# GCM_SCH.net
KiCad netlist of a schematic drawn in Altium Designer
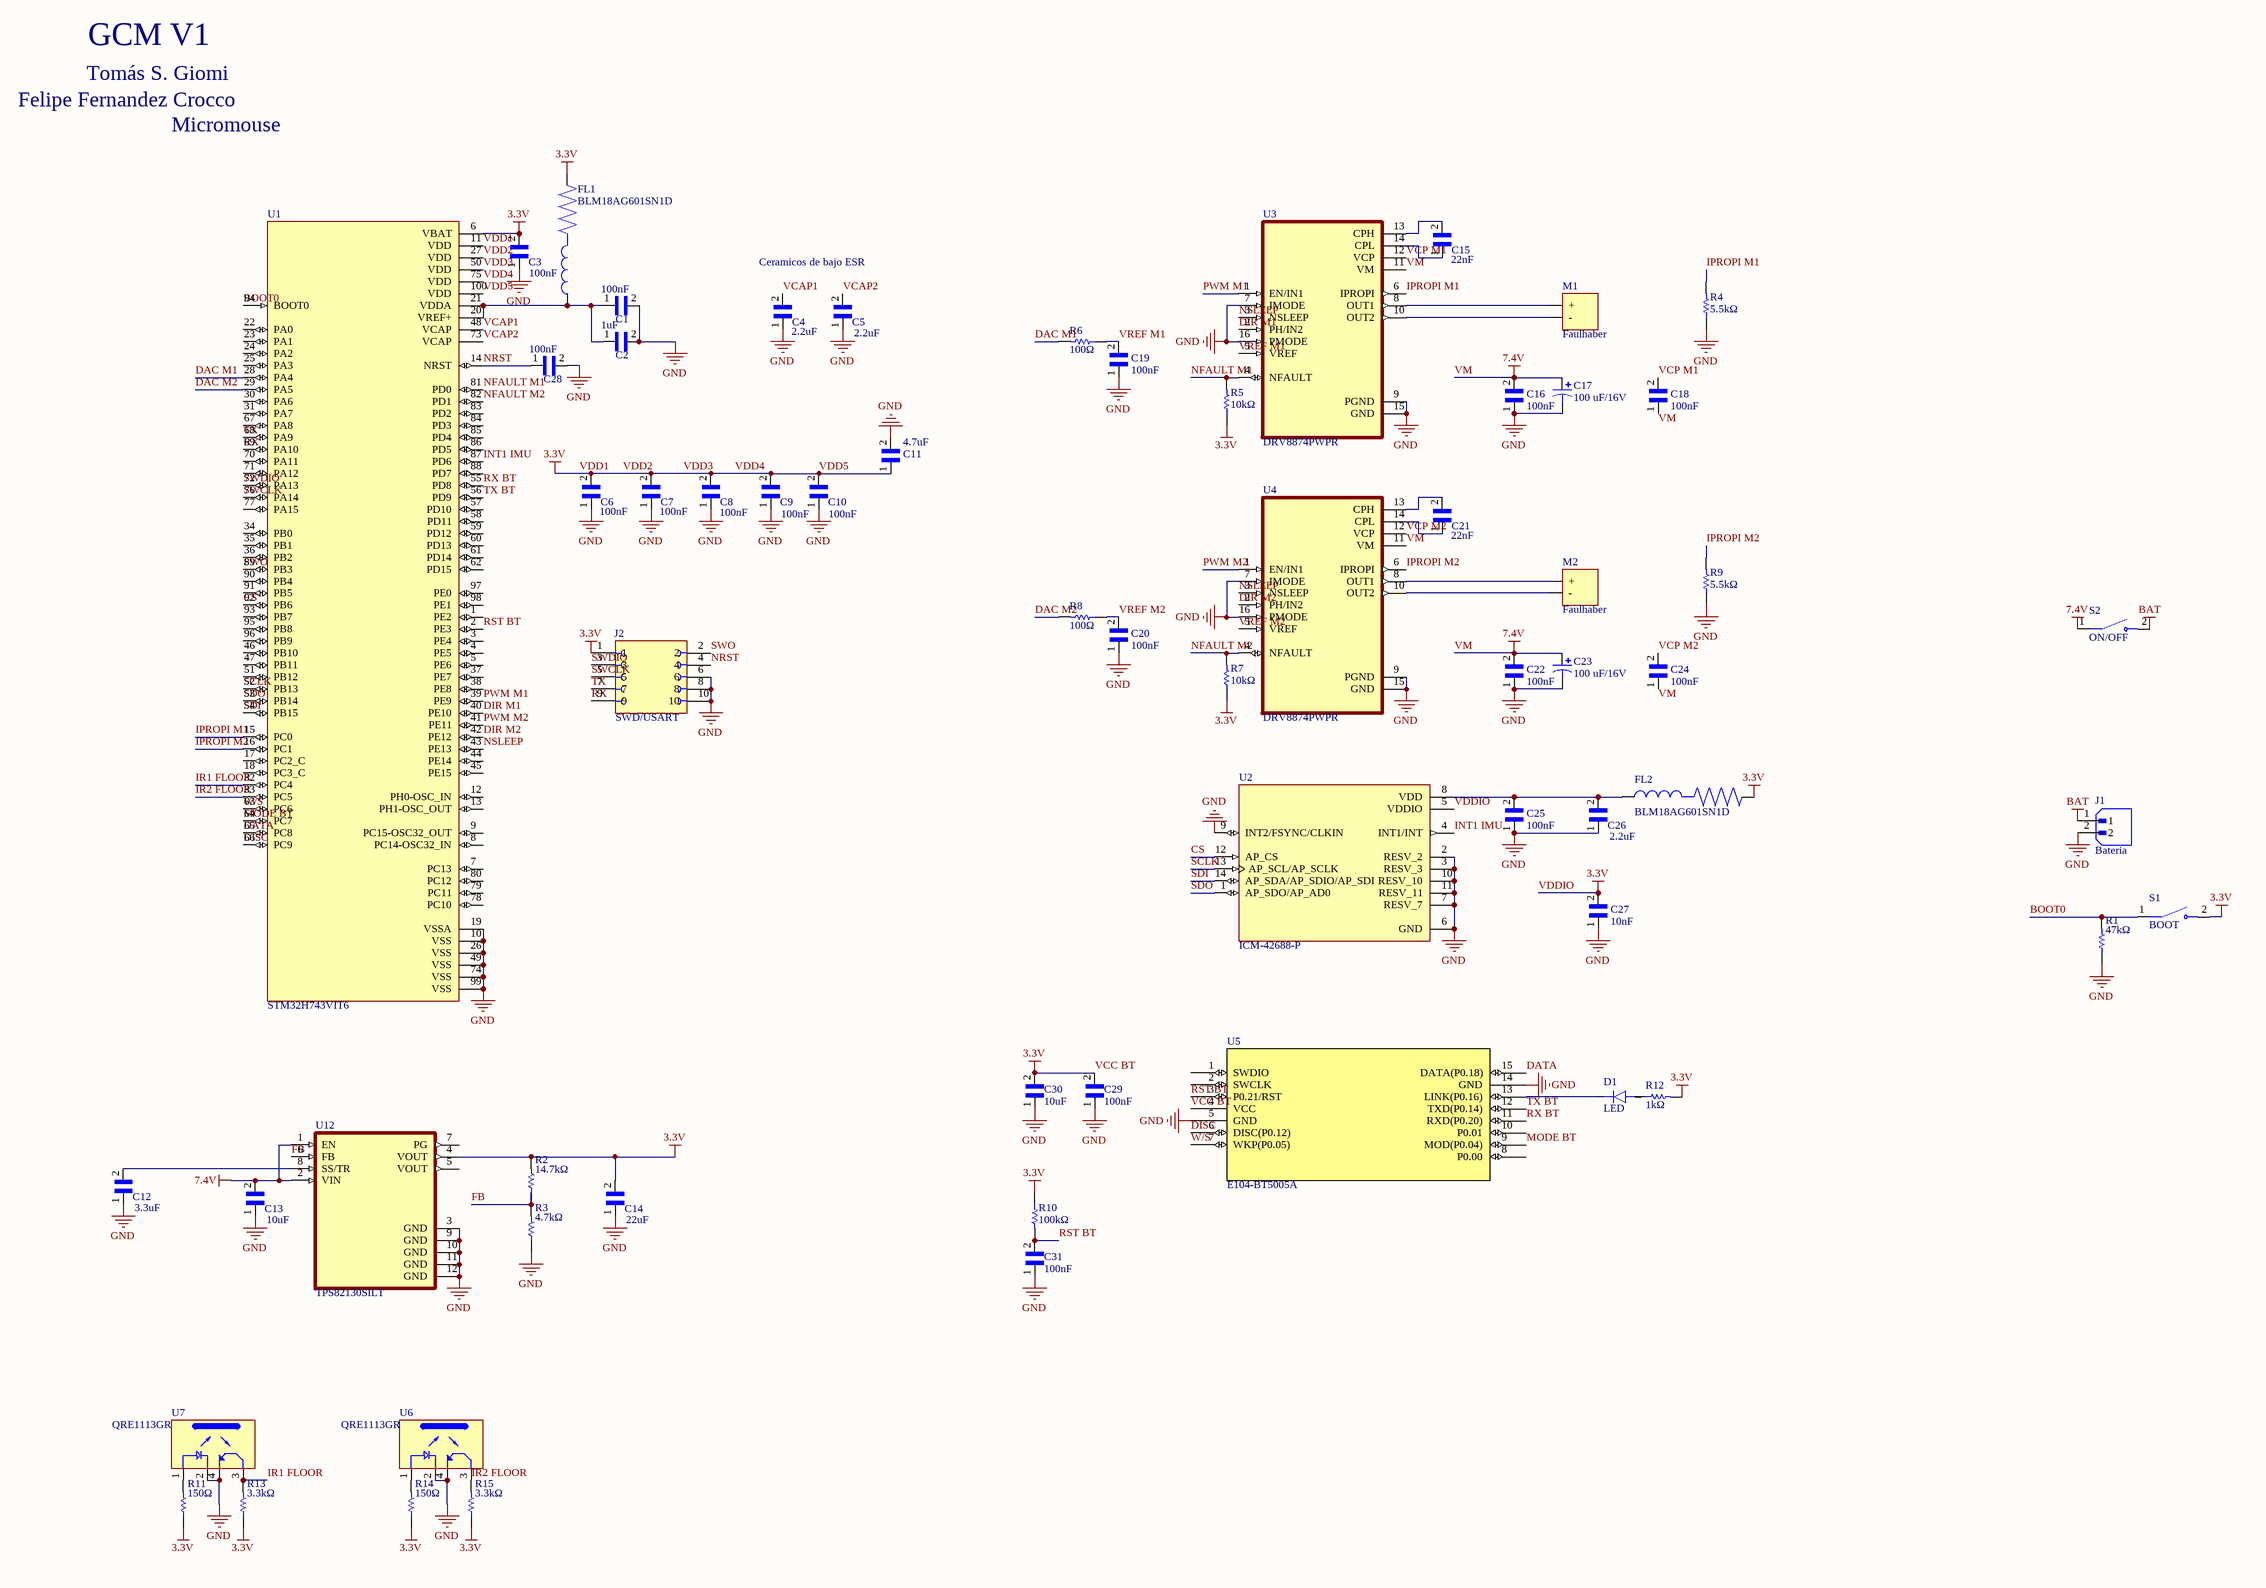
[diagram p0: GCM_SCH.SchDoc]

(export (version "E")
  (design (tool "Eeschema 10.0.6"))
  (components
    (comp (ref "C1")
      (value "100nF")
      (footprint "CAPACITOR TANTALIO")
      (description "0805")
      (fields (field (name "MP") "GRM035R60J475ME15D") (field (name "MF") "Murata"))
      (libsource (lib "") (part "CAPACITOR TANTALIO_1"))
    )
    (comp (ref "C2")
      (value "1uF")
      (footprint "CAPACITOR TANTALIO")
      (description "0805")
      (fields (field (name "MP") "GRM035R60J475ME15D") (field (name "MF") "Murata"))
      (libsource (lib "") (part "CAPACITOR TANTALIO_1"))
    )
    (comp (ref "C3")
      (value "100nF")
      (footprint "CAPACITOR TANTALIO")
      (description "0805")
      (fields (field (name "MP") "GRM035R60J475ME15D") (field (name "MF") "Murata"))
      (libsource (lib "GCMLibreriasSCH") (part "CAPACITOR TANTALIO"))
    )
    (comp (ref "C4")
      (value "2.2uF")
      (footprint "CAPACITOR TANTALIO")
      (description "0805")
      (fields (field (name "MP") "GRM035R60J475ME15D") (field (name "MF") "Murata"))
      (libsource (lib "GCMLibreriasSCH") (part "CAPACITOR TANTALIO"))
    )
    (comp (ref "C5")
      (value "2.2uF")
      (footprint "CAPACITOR TANTALIO")
      (description "0805")
      (fields (field (name "MP") "GRM035R60J475ME15D") (field (name "MF") "Murata"))
      (libsource (lib "GCMLibreriasSCH") (part "CAPACITOR TANTALIO"))
    )
    (comp (ref "C6")
      (value "100nF")
      (footprint "CAPACITOR TANTALIO")
      (description "0805")
      (fields (field (name "MP") "GRM035R60J475ME15D") (field (name "MF") "Murata"))
      (libsource (lib "GCMLibreriasSCH") (part "CAPACITOR TANTALIO"))
    )
    (comp (ref "C7")
      (value "100nF")
      (footprint "CAPACITOR TANTALIO")
      (description "0805")
      (fields (field (name "MP") "GRM035R60J475ME15D") (field (name "MF") "Murata"))
      (libsource (lib "GCMLibreriasSCH") (part "CAPACITOR TANTALIO"))
    )
    (comp (ref "C8")
      (value "100nF")
      (footprint "CAPACITOR TANTALIO")
      (description "0805")
      (fields (field (name "MP") "GRM035R60J475ME15D") (field (name "MF") "Murata"))
      (libsource (lib "GCMLibreriasSCH") (part "CAPACITOR TANTALIO"))
    )
    (comp (ref "C9")
      (value "100nF")
      (footprint "CAPACITOR TANTALIO")
      (description "0805")
      (fields (field (name "MP") "GRM035R60J475ME15D") (field (name "MF") "Murata"))
      (libsource (lib "GCMLibreriasSCH") (part "CAPACITOR TANTALIO"))
    )
    (comp (ref "C10")
      (value "100nF")
      (footprint "CAPACITOR TANTALIO")
      (description "0805")
      (fields (field (name "MP") "GRM035R60J475ME15D") (field (name "MF") "Murata"))
      (libsource (lib "GCMLibreriasSCH") (part "CAPACITOR TANTALIO"))
    )
    (comp (ref "C11")
      (value "4.7uF")
      (footprint "CAPACITOR TANTALIO")
      (description "0805")
      (fields (field (name "MP") "GRM035R60J475ME15D") (field (name "MF") "Murata"))
      (libsource (lib "GCMLibreriasSCH") (part "CAPACITOR TANTALIO"))
    )
    (comp (ref "C12")
      (value "3.3uF")
      (footprint "CAPACITOR TANTALIO")
      (description "0805")
      (fields (field (name "MP") "GRM035R60J475ME15D") (field (name "MF") "Murata"))
      (libsource (lib "GCMLibreriasSCH") (part "CAPACITOR TANTALIO"))
    )
    (comp (ref "C13")
      (value "10uF")
      (footprint "CAPACITOR TANTALIO")
      (description "0805")
      (fields (field (name "MP") "GRM035R60J475ME15D") (field (name "MF") "Murata"))
      (libsource (lib "GCMLibreriasSCH") (part "CAPACITOR TANTALIO"))
    )
    (comp (ref "C14")
      (value "22uF")
      (footprint "CAPACITOR TANTALIO")
      (description "0805")
      (fields (field (name "MP") "GRM035R60J475ME15D") (field (name "MF") "Murata"))
      (libsource (lib "GCMLibreriasSCH") (part "CAPACITOR TANTALIO"))
    )
    (comp (ref "C15")
      (value "22nF")
      (footprint "CAPACITOR TANTALIO")
      (description "0805")
      (fields (field (name "MP") "GRM035R60J475ME15D") (field (name "MF") "Murata"))
      (libsource (lib "GCMLibreriasSCH") (part "CAPACITOR TANTALIO"))
    )
    (comp (ref "C16")
      (value "100nF")
      (footprint "CAPACITOR TANTALIO")
      (description "0805")
      (fields (field (name "MP") "GRM035R60J475ME15D") (field (name "MF") "Murata"))
      (libsource (lib "GCMLibreriasSCH") (part "CAPACITOR TANTALIO"))
    )
    (comp (ref "C17")
      (value "100 uF/16V")
      (footprint "Cap El 10uF")
      (libsource (lib "GCMLibreriasSCH") (part "Cap el 10 uF"))
    )
    (comp (ref "C18")
      (value "100nF")
      (footprint "CAPACITOR TANTALIO")
      (description "0805")
      (fields (field (name "MP") "GRM035R60J475ME15D") (field (name "MF") "Murata"))
      (libsource (lib "GCMLibreriasSCH") (part "CAPACITOR TANTALIO"))
    )
    (comp (ref "C19")
      (value "100nF")
      (footprint "CAPACITOR TANTALIO")
      (description "0805")
      (fields (field (name "MP") "GRM035R60J475ME15D") (field (name "MF") "Murata"))
      (libsource (lib "GCMLibreriasSCH") (part "CAPACITOR TANTALIO"))
    )
    (comp (ref "C20")
      (value "100nF")
      (footprint "CAPACITOR TANTALIO")
      (description "0805")
      (fields (field (name "MP") "GRM035R60J475ME15D") (field (name "MF") "Murata"))
      (libsource (lib "GCMLibreriasSCH") (part "CAPACITOR TANTALIO"))
    )
    (comp (ref "C21")
      (value "22nF")
      (footprint "CAPACITOR TANTALIO")
      (description "0805")
      (fields (field (name "MP") "GRM035R60J475ME15D") (field (name "MF") "Murata"))
      (libsource (lib "GCMLibreriasSCH") (part "CAPACITOR TANTALIO"))
    )
    (comp (ref "C22")
      (value "100nF")
      (footprint "CAPACITOR TANTALIO")
      (description "0805")
      (fields (field (name "MP") "GRM035R60J475ME15D") (field (name "MF") "Murata"))
      (libsource (lib "GCMLibreriasSCH") (part "CAPACITOR TANTALIO"))
    )
    (comp (ref "C23")
      (value "100 uF/16V")
      (footprint "Cap El 10uF")
      (libsource (lib "GCMLibreriasSCH") (part "Cap el 10 uF"))
    )
    (comp (ref "C24")
      (value "100nF")
      (footprint "CAPACITOR TANTALIO")
      (description "0805")
      (fields (field (name "MP") "GRM035R60J475ME15D") (field (name "MF") "Murata"))
      (libsource (lib "GCMLibreriasSCH") (part "CAPACITOR TANTALIO"))
    )
    (comp (ref "C25")
      (value "100nF")
      (footprint "CAPACITOR TANTALIO")
      (description "0805")
      (fields (field (name "MP") "GRM035R60J475ME15D") (field (name "MF") "Murata"))
      (libsource (lib "GCMLibreriasSCH") (part "CAPACITOR TANTALIO"))
    )
    (comp (ref "C26")
      (value "2.2uF")
      (footprint "CAPACITOR TANTALIO")
      (description "0805")
      (fields (field (name "MP") "GRM035R60J475ME15D") (field (name "MF") "Murata"))
      (libsource (lib "GCMLibreriasSCH") (part "CAPACITOR TANTALIO"))
    )
    (comp (ref "C27")
      (value "10nF")
      (footprint "CAPACITOR TANTALIO")
      (description "0805")
      (fields (field (name "MP") "GRM035R60J475ME15D") (field (name "MF") "Murata"))
      (libsource (lib "GCMLibreriasSCH") (part "CAPACITOR TANTALIO"))
    )
    (comp (ref "C28")
      (value "100nF")
      (footprint "CAPACITOR TANTALIO")
      (description "0805")
      (fields (field (name "MP") "GRM035R60J475ME15D") (field (name "MF") "Murata"))
      (libsource (lib "") (part "CAPACITOR TANTALIO_1"))
    )
    (comp (ref "C29")
      (value "100nF")
      (footprint "CAPACITOR TANTALIO")
      (description "0805")
      (fields (field (name "MP") "GRM035R60J475ME15D") (field (name "MF") "Murata"))
      (libsource (lib "GCMLibreriasSCH") (part "CAPACITOR TANTALIO"))
    )
    (comp (ref "C30")
      (value "10uF")
      (footprint "CAPACITOR TANTALIO")
      (description "0805")
      (fields (field (name "MP") "GRM035R60J475ME15D") (field (name "MF") "Murata"))
      (libsource (lib "GCMLibreriasSCH") (part "CAPACITOR TANTALIO"))
    )
    (comp (ref "C31")
      (value "100nF")
      (footprint "CAPACITOR TANTALIO")
      (description "0805")
      (fields (field (name "MP") "GRM035R60J475ME15D") (field (name "MF") "Murata"))
      (libsource (lib "GCMLibreriasSCH") (part "CAPACITOR TANTALIO"))
    )
    (comp (ref "D1")
      (value "LED")
      (footprint "LED SMD")
      (description "0805")
      (fields (field (name "MP") "597-5311-402F"))
      (libsource (lib "GCMLibreriasSCH") (part "LED SMD"))
    )
    (comp (ref "FL1")
      (value "BLM18AG601SN1D")
      (footprint "BEADC1608X95N")
      (description "600 Ohms @ 100 MHz 1 - Ferrite Bead 0603 (1608 Metric) 500mA 380mOhm")
      (fields (field (name "MF") "Murata"))
      (libsource (lib "GCMLibreriasSCH") (part "BLM18AG601SN1D"))
    )
    (comp (ref "FL2")
      (value "BLM18AG601SN1D")
      (footprint "BEADC1608X95N")
      (description "600 Ohms @ 100 MHz 1 - Ferrite Bead 0603 (1608 Metric) 500mA 380mOhm")
      (fields (field (name "MF") "Murata"))
      (libsource (lib "GCMLibreriasSCH") (part "BLM18AG601SN1D"))
    )
    (comp (ref "J1")
      (value "Bateria")
      (footprint "JST_B2B-XH-A")
      (fields
        (field (name "MF") "{'manufacturer': u'JST Sales America Inc.'}")
        (field (name "MP") "B2B-XH-A")
      )
      (libsource (lib "GCMLibreriasSCH") (part "B2B-XH-A"))
    )
    (comp (ref "J2")
      (value "SWD/USART")
      (footprint "AMPHENOL_20021311-00026T4LF")
      (fields (field (name "MF") "Amphenol ICC") (field (name "MP") "20021311-00026T4LF"))
      (libsource (lib "GCMLibreriasSCH") (part "20021311-00026T4LF"))
    )
    (comp (ref "M1")
      (value "Faulhaber")
      (footprint "MOTOR")
      (fields (field (name "PUBLISHER") "Altium Limited"))
      (libsource (lib "GCMLibreriasSCH") (part "Faulhaber"))
    )
    (comp (ref "M2")
      (value "Faulhaber")
      (footprint "MOTOR")
      (fields (field (name "PUBLISHER") "Altium Limited"))
      (libsource (lib "GCMLibreriasSCH") (part "Faulhaber"))
    )
    (comp (ref "R1")
      (value "47kΩ")
      (footprint "RESISTENCIA SMD")
      (description "0805")
      (fields (field (name "PUBLISHER") "Altium Limited"))
      (libsource (lib "GCMLibreriasSCH") (part "RESISTENCIA"))
    )
    (comp (ref "R2")
      (value "14.7kΩ")
      (footprint "RESISTENCIA SMD")
      (description "0805")
      (fields (field (name "PUBLISHER") "Altium Limited"))
      (libsource (lib "GCMLibreriasSCH") (part "RESISTENCIA"))
    )
    (comp (ref "R3")
      (value "4.7kΩ")
      (footprint "RESISTENCIA SMD")
      (description "0805")
      (fields (field (name "PUBLISHER") "Altium Limited"))
      (libsource (lib "GCMLibreriasSCH") (part "RESISTENCIA"))
    )
    (comp (ref "R4")
      (value "5.5kΩ")
      (footprint "RESISTENCIA SMD")
      (description "0805")
      (fields (field (name "PUBLISHER") "Altium Limited"))
      (libsource (lib "GCMLibreriasSCH") (part "RESISTENCIA"))
    )
    (comp (ref "R5")
      (value "10kΩ")
      (footprint "RESISTENCIA SMD")
      (description "0805")
      (fields (field (name "PUBLISHER") "Altium Limited"))
      (libsource (lib "GCMLibreriasSCH") (part "RESISTENCIA"))
    )
    (comp (ref "R6")
      (value "100Ω")
      (footprint "RESISTENCIA SMD")
      (description "0805")
      (fields (field (name "PUBLISHER") "Altium Limited"))
      (libsource (lib "GCMLibreriasSCH") (part "RESISTENCIA"))
    )
    (comp (ref "R7")
      (value "10kΩ")
      (footprint "RESISTENCIA SMD")
      (description "0805")
      (fields (field (name "PUBLISHER") "Altium Limited"))
      (libsource (lib "GCMLibreriasSCH") (part "RESISTENCIA"))
    )
    (comp (ref "R8")
      (value "100Ω")
      (footprint "RESISTENCIA SMD")
      (description "0805")
      (fields (field (name "PUBLISHER") "Altium Limited"))
      (libsource (lib "GCMLibreriasSCH") (part "RESISTENCIA"))
    )
    (comp (ref "R9")
      (value "5.5kΩ")
      (footprint "RESISTENCIA SMD")
      (description "0805")
      (fields (field (name "PUBLISHER") "Altium Limited"))
      (libsource (lib "GCMLibreriasSCH") (part "RESISTENCIA"))
    )
    (comp (ref "R10")
      (value "100kΩ")
      (footprint "RESISTENCIA SMD")
      (description "0805")
      (fields (field (name "PUBLISHER") "Altium Limited"))
      (libsource (lib "GCMLibreriasSCH") (part "RESISTENCIA"))
    )
    (comp (ref "R11")
      (value "150Ω")
      (footprint "RESISTENCIA SMD")
      (description "0805")
      (fields (field (name "PUBLISHER") "Altium Limited"))
      (libsource (lib "GCMLibreriasSCH") (part "RESISTENCIA"))
    )
    (comp (ref "R12")
      (value "1kΩ")
      (footprint "RESISTENCIA SMD")
      (description "0805")
      (fields (field (name "PUBLISHER") "Altium Limited"))
      (libsource (lib "GCMLibreriasSCH") (part "RESISTENCIA"))
    )
    (comp (ref "R13")
      (value "3.3kΩ")
      (footprint "RESISTENCIA SMD")
      (description "0805")
      (fields (field (name "PUBLISHER") "Altium Limited"))
      (libsource (lib "GCMLibreriasSCH") (part "RESISTENCIA"))
    )
    (comp (ref "R14")
      (value "150Ω")
      (footprint "RESISTENCIA SMD")
      (description "0805")
      (fields (field (name "PUBLISHER") "Altium Limited"))
      (libsource (lib "GCMLibreriasSCH") (part "RESISTENCIA"))
    )
    (comp (ref "R15")
      (value "3.3kΩ")
      (footprint "RESISTENCIA SMD")
      (description "0805")
      (fields (field (name "PUBLISHER") "Altium Limited"))
      (libsource (lib "GCMLibreriasSCH") (part "RESISTENCIA"))
    )
    (comp (ref "S1")
      (value "BOOT")
      (footprint "SW_TS09-63-25-WT-160-SMT-TR")
      (description "6.1 x 3.7 mm, 2.5 mm Actuator Height, 160 gf, White, Surface Mount, SPST, Tactile Switch")
      (fields (field (name "MF") "Same Sky") (field (name "MP") "TS09-63-25-WT-160-SMT-TR"))
      (libsource (lib "GCMLibreriasSCH") (part "TS09-63-25-WT-160-SMT-TR"))
    )
    (comp (ref "S2")
      (value "ON/OFF")
      (footprint "SW_L101011ML04Q")
      (description "Switch Slide ON OFF SPST Side Slide 4A 250VAC 125VDC PC Pins Thru-Hole Bulk")
      (fields (field (name "MF") "C&K") (field (name "MP") "L101011ML04Q"))
      (libsource (lib "GCMLibreriasSCH") (part "L101011ML04Q"))
    )
    (comp (ref "U1")
      (value "STM32H743VIT6")
      (footprint "QFP50P1600X1600X160-100N")
      (fields (field (name "MF") "STMicroelectronics"))
      (libsource (lib "GCMLibreriasSCH") (part "STM32H743VIT6"))
    )
    (comp (ref "U2")
      (value "ICM-42688-P")
      (footprint "GCMLibreriasPCB:PQFN50P300X250X97-14N")
      (description "Accelerometer, Gyroscope, 6 Axis Sensor Output")
      (libsource (lib "GCMLibreriasSCH") (part "ICM-42688-P"))
    )
    (comp (ref "U3")
      (value "DRV8874PWPR")
      (footprint "SOP65P640X120-17N")
      (description "40-V, 6-A H-bridge motor driver with integrated current sensing feedback")
      (fields (field (name "MF") "Texas Instruments"))
      (libsource (lib "GCMLibreriasSCH") (part "DRV8874PWPR"))
    )
    (comp (ref "U4")
      (value "DRV8874PWPR")
      (footprint "SOP65P640X120-17N")
      (description "40-V, 6-A H-bridge motor driver with integrated current sensing feedback")
      (fields (field (name "MF") "Texas Instruments"))
      (libsource (lib "GCMLibreriasSCH") (part "DRV8874PWPR"))
    )
    (comp (ref "U5")
      (value "E104-BT5005A")
      (footprint "MOD15_E104-BT5005A_BYT")
      (description "No Description Available")
      (fields (field (name "COPYRIGHT") "Copyright (C) 2026 Ultra Librarian. All rights reserved."))
      (libsource (lib "GCMLibreriasSCH") (part "E104-BT5005A"))
    )
    (comp (ref "U6")
      (value "QRE1113GR")
      (footprint "SOIC180P460X187-4N")
      (description "Reflective Optical Sensor 0.039 (1mm) 4-SMD, Gull Wing")
      (fields (field (name "MF") "ON Semiconductor"))
      (libsource (lib "GCMLibreriasSCH") (part "QRE1113GR"))
    )
    (comp (ref "U7")
      (value "QRE1113GR")
      (footprint "SOIC180P460X187-4N")
      (description "Reflective Optical Sensor 0.039 (1mm) 4-SMD, Gull Wing")
      (fields (field (name "MF") "ON Semiconductor"))
      (libsource (lib "GCMLibreriasSCH") (part "QRE1113GR"))
    )
    (comp (ref "U12")
      (value "TPS82130SILT")
      (footprint "CONV_TPS82140SILR")
      (description "Non-Isolated PoL Module DC DC Converter 1 Output 0.9 ~ 5V - - - 3A 3V - 17V Input")
      (fields (field (name "MF") "Texas Instruments") (field (name "MP") "TPS82130SIL"))
      (libsource (lib "GCMLibreriasSCH") (part "TPS82130SILT"))
    )
  )
  (nets
    (net (code "1") (name "/BOOT0") (class "Default")
      (node (ref "R1") (pin "2") (pinfunction "2_2") (pintype "passive"))
      (node (ref "S1") (pin "1") (pinfunction "1_1") (pintype "passive"))
      (node (ref "U1") (pin "94") (pinfunction "BOOT0_94") (pintype "input"))
    )
    (net (code "2") (name "/CS") (class "Default")
      (node (ref "U1") (pin "92") (pinfunction "PB6_92") (pintype "bidirectional"))
      (node (ref "U2") (pin "12") (pinfunction "AP_CS_12") (pintype "input"))
    )
    (net (code "3") (name "/DAC M1") (class "Default")
      (node (ref "R6") (pin "2") (pinfunction "2_2") (pintype "passive"))
      (node (ref "U1") (pin "28") (pinfunction "PA4_28") (pintype "bidirectional"))
    )
    (net (code "4") (name "/DAC M2") (class "Default")
      (node (ref "R8") (pin "2") (pinfunction "2_2") (pintype "passive"))
      (node (ref "U1") (pin "29") (pinfunction "PA5_29") (pintype "bidirectional"))
    )
    (net (code "5") (name "/DATA") (class "Default")
      (node (ref "U1") (pin "65") (pinfunction "PC8_65") (pintype "bidirectional"))
      (node (ref "U5") (pin "15") (pinfunction "DATA(P0.18)_15") (pintype "bidirectional"))
    )
    (net (code "6") (name "/DIR M1") (class "Default")
      (node (ref "U1") (pin "40") (pinfunction "PE10_40") (pintype "bidirectional"))
      (node (ref "U3") (pin "2") (pinfunction "PH/IN2_2") (pintype "input"))
    )
    (net (code "7") (name "/DIR M2") (class "Default")
      (node (ref "U1") (pin "42") (pinfunction "PE12_42") (pintype "bidirectional"))
      (node (ref "U4") (pin "2") (pinfunction "PH/IN2_2") (pintype "input"))
    )
    (net (code "8") (name "/DISC") (class "Default")
      (node (ref "U1") (pin "66") (pinfunction "PC9_66") (pintype "bidirectional"))
      (node (ref "U5") (pin "6") (pinfunction "DISC(P0.12)_6") (pintype "bidirectional"))
    )
    (net (code "9") (name "/FB") (class "Default")
      (node (ref "R2") (pin "1") (pinfunction "1_1") (pintype "passive"))
      (node (ref "R3") (pin "2") (pinfunction "2_2") (pintype "passive"))
      (node (ref "U12") (pin "6") (pinfunction "FB_6") (pintype "input"))
    )
    (net (code "10") (name "/INT1 IMU") (class "Default")
      (node (ref "U1") (pin "87") (pinfunction "PD6_87") (pintype "bidirectional"))
      (node (ref "U2") (pin "4") (pinfunction "INT1/INT_4") (pintype "output"))
    )
    (net (code "11") (name "/IPROPI M1") (class "Default")
      (node (ref "R4") (pin "2") (pinfunction "2_2") (pintype "passive"))
      (node (ref "U1") (pin "15") (pinfunction "PC0_15") (pintype "bidirectional"))
      (node (ref "U3") (pin "6") (pinfunction "IPROPI_6") (pintype "output"))
    )
    (net (code "12") (name "/IPROPI M2") (class "Default")
      (node (ref "R9") (pin "2") (pinfunction "2_2") (pintype "passive"))
      (node (ref "U1") (pin "16") (pinfunction "PC1_16") (pintype "bidirectional"))
      (node (ref "U4") (pin "6") (pinfunction "IPROPI_6") (pintype "output"))
    )
    (net (code "13") (name "/IR1 FLOOR") (class "Default")
      (node (ref "R13") (pin "2") (pinfunction "2_2") (pintype "passive"))
      (node (ref "U1") (pin "32") (pinfunction "PC4_32") (pintype "bidirectional"))
      (node (ref "U7") (pin "3") (pinfunction "CT_3") (pintype "passive"))
    )
    (net (code "14") (name "/IR2 FLOOR") (class "Default")
      (node (ref "R15") (pin "2") (pinfunction "2_2") (pintype "passive"))
      (node (ref "U1") (pin "33") (pinfunction "PC5_33") (pintype "bidirectional"))
      (node (ref "U6") (pin "3") (pinfunction "CT_3") (pintype "passive"))
    )
    (net (code "15") (name "/MODE BT") (class "Default")
      (node (ref "U1") (pin "64") (pinfunction "PC7_64") (pintype "bidirectional"))
      (node (ref "U5") (pin "9") (pinfunction "MOD(P0.04)_9") (pintype "bidirectional"))
    )
    (net (code "16") (name "/NFAULT M1") (class "Default")
      (node (ref "R5") (pin "2") (pinfunction "2_2") (pintype "passive"))
      (node (ref "U1") (pin "81") (pinfunction "PD0_81") (pintype "bidirectional"))
      (node (ref "U3") (pin "4") (pinfunction "NFAULT_4") (pintype "bidirectional"))
    )
    (net (code "17") (name "/NFAULT M2") (class "Default")
      (node (ref "R7") (pin "2") (pinfunction "2_2") (pintype "passive"))
      (node (ref "U1") (pin "82") (pinfunction "PD1_82") (pintype "bidirectional"))
      (node (ref "U4") (pin "4") (pinfunction "NFAULT_4") (pintype "bidirectional"))
    )
    (net (code "18") (name "/NRST") (class "Default")
      (node (ref "C28") (pin "1") (pinfunction "1_1") (pintype "passive"))
      (node (ref "J2") (pin "4") (pinfunction "4_4") (pintype "passive"))
      (node (ref "U1") (pin "14") (pinfunction "NRST_14") (pintype "bidirectional"))
    )
    (net (code "19") (name "/NSLEEP") (class "Default")
      (node (ref "U1") (pin "43") (pinfunction "PE13_43") (pintype "bidirectional"))
      (node (ref "U3") (pin "3") (pinfunction "NSLEEP_3") (pintype "input"))
      (node (ref "U4") (pin "3") (pinfunction "NSLEEP_3") (pintype "input"))
    )
    (net (code "20") (name "/PWM M1") (class "Default")
      (node (ref "U1") (pin "39") (pinfunction "PE9_39") (pintype "bidirectional"))
      (node (ref "U3") (pin "1") (pinfunction "EN/IN1_1") (pintype "input"))
    )
    (net (code "21") (name "/PWM M2") (class "Default")
      (node (ref "U1") (pin "41") (pinfunction "PE11_41") (pintype "bidirectional"))
      (node (ref "U4") (pin "1") (pinfunction "EN/IN1_1") (pintype "input"))
    )
    (net (code "22") (name "/RST BT") (class "Default")
      (node (ref "C31") (pin "2") (pinfunction "2_2") (pintype "passive"))
      (node (ref "R10") (pin "2") (pinfunction "2_2") (pintype "passive"))
      (node (ref "U1") (pin "2") (pinfunction "PE3_2") (pintype "bidirectional"))
      (node (ref "U5") (pin "3") (pinfunction "P0.21/RST_3") (pintype "bidirectional"))
    )
    (net (code "23") (name "/RX") (class "Default")
      (node (ref "J2") (pin "9") (pinfunction "9_9") (pintype "passive"))
      (node (ref "U1") (pin "69") (pinfunction "PA10_69") (pintype "bidirectional"))
    )
    (net (code "24") (name "/RX BT") (class "Default")
      (node (ref "U1") (pin "55") (pinfunction "PD8_55") (pintype "bidirectional"))
      (node (ref "U5") (pin "11") (pinfunction "RXD(P0.20)_11") (pintype "bidirectional"))
    )
    (net (code "25") (name "/SCLK") (class "Default")
      (node (ref "U1") (pin "52") (pinfunction "PB13_52") (pintype "bidirectional"))
      (node (ref "U2") (pin "13") (pinfunction "AP_SCL/AP_SCLK_13") (pintype "input"))
    )
    (net (code "26") (name "/SDI") (class "Default")
      (node (ref "U1") (pin "54") (pinfunction "PB15_54") (pintype "bidirectional"))
      (node (ref "U2") (pin "14") (pinfunction "AP_SDA/AP_SDIO/AP_SDI_14") (pintype "bidirectional"))
    )
    (net (code "27") (name "/SDO") (class "Default")
      (node (ref "U1") (pin "53") (pinfunction "PB14_53") (pintype "bidirectional"))
      (node (ref "U2") (pin "1") (pinfunction "AP_SDO/AP_AD0_1") (pintype "bidirectional"))
    )
    (net (code "28") (name "/SWCLK") (class "Default")
      (node (ref "J2") (pin "5") (pinfunction "5_5") (pintype "passive"))
      (node (ref "U1") (pin "76") (pinfunction "PA14_76") (pintype "bidirectional"))
    )
    (net (code "29") (name "/SWDIO") (class "Default")
      (node (ref "J2") (pin "3") (pinfunction "3_3") (pintype "passive"))
      (node (ref "U1") (pin "72") (pinfunction "PA13_72") (pintype "bidirectional"))
    )
    (net (code "30") (name "/SWO") (class "Default")
      (node (ref "J2") (pin "2") (pinfunction "2_2") (pintype "passive"))
      (node (ref "U1") (pin "89") (pinfunction "PB3_89") (pintype "bidirectional"))
    )
    (net (code "31") (name "/TX") (class "Default")
      (node (ref "J2") (pin "7") (pinfunction "7_7") (pintype "passive"))
      (node (ref "U1") (pin "68") (pinfunction "PA9_68") (pintype "bidirectional"))
    )
    (net (code "32") (name "/TX BT") (class "Default")
      (node (ref "U1") (pin "56") (pinfunction "PD9_56") (pintype "bidirectional"))
      (node (ref "U5") (pin "12") (pinfunction "TXD(P0.14)_12") (pintype "bidirectional"))
    )
    (net (code "33") (name "/VCAP1") (class "Default")
      (node (ref "C4") (pin "2") (pinfunction "2_2") (pintype "passive"))
      (node (ref "U1") (pin "48") (pinfunction "VCAP_48") (pintype "power_in"))
    )
    (net (code "34") (name "/VCAP2") (class "Default")
      (node (ref "C5") (pin "2") (pinfunction "2_2") (pintype "passive"))
      (node (ref "U1") (pin "73") (pinfunction "VCAP_73") (pintype "power_in"))
    )
    (net (code "35") (name "/VCP M1") (class "Default")
      (node (ref "C18") (pin "2") (pinfunction "2_2") (pintype "passive"))
      (node (ref "U3") (pin "12") (pinfunction "VCP_12") (pintype "power_in"))
    )
    (net (code "36") (name "/VCP M2") (class "Default")
      (node (ref "C24") (pin "2") (pinfunction "2_2") (pintype "passive"))
      (node (ref "U4") (pin "12") (pinfunction "VCP_12") (pintype "power_in"))
    )
    (net (code "37") (name "/VREF M1") (class "Default")
      (node (ref "C19") (pin "2") (pinfunction "2_2") (pintype "passive"))
      (node (ref "R6") (pin "1") (pinfunction "1_1") (pintype "passive"))
      (node (ref "U3") (pin "5") (pinfunction "VREF_5") (pintype "input"))
    )
    (net (code "38") (name "/VREF M2") (class "Default")
      (node (ref "C20") (pin "2") (pinfunction "2_2") (pintype "passive"))
      (node (ref "R8") (pin "1") (pinfunction "1_1") (pintype "passive"))
      (node (ref "U4") (pin "5") (pinfunction "VREF_5") (pintype "input"))
    )
    (net (code "39") (name "/W{slash}S") (class "Default")
      (node (ref "U1") (pin "63") (pinfunction "PC6_63") (pintype "bidirectional"))
      (node (ref "U5") (pin "7") (pinfunction "WKP(P0.05)_7") (pintype "bidirectional"))
    )
    (net (code "40") (name "3.3V") (class "Default")
      (node (ref "C10") (pin "2") (pinfunction "2_2") (pintype "passive"))
      (node (ref "C11") (pin "1") (pinfunction "1_1") (pintype "passive"))
      (node (ref "C14") (pin "2") (pinfunction "2_2") (pintype "passive"))
      (node (ref "C27") (pin "2") (pinfunction "2_2") (pintype "passive"))
      (node (ref "C29") (pin "2") (pinfunction "2_2") (pintype "passive"))
      (node (ref "C3") (pin "2") (pinfunction "2_2") (pintype "passive"))
      (node (ref "C30") (pin "2") (pinfunction "2_2") (pintype "passive"))
      (node (ref "C6") (pin "2") (pinfunction "2_2") (pintype "passive"))
      (node (ref "C7") (pin "2") (pinfunction "2_2") (pintype "passive"))
      (node (ref "C8") (pin "2") (pinfunction "2_2") (pintype "passive"))
      (node (ref "C9") (pin "2") (pinfunction "2_2") (pintype "passive"))
      (node (ref "FL1") (pin "2") (pinfunction "2_2") (pintype "passive"))
      (node (ref "FL2") (pin "2") (pinfunction "2_2") (pintype "passive"))
      (node (ref "J2") (pin "1") (pinfunction "1_1") (pintype "passive"))
      (node (ref "R10") (pin "1") (pinfunction "1_1") (pintype "passive"))
      (node (ref "R11") (pin "1") (pinfunction "1_1") (pintype "passive"))
      (node (ref "R12") (pin "2") (pinfunction "2_2") (pintype "passive"))
      (node (ref "R13") (pin "1") (pinfunction "1_1") (pintype "passive"))
      (node (ref "R14") (pin "1") (pinfunction "1_1") (pintype "passive"))
      (node (ref "R15") (pin "1") (pinfunction "1_1") (pintype "passive"))
      (node (ref "R2") (pin "2") (pinfunction "2_2") (pintype "passive"))
      (node (ref "R5") (pin "1") (pinfunction "1_1") (pintype "passive"))
      (node (ref "R7") (pin "1") (pinfunction "1_1") (pintype "passive"))
      (node (ref "S1") (pin "2") (pinfunction "2_2") (pintype "passive"))
      (node (ref "U1") (pin "100") (pinfunction "VDD_100") (pintype "power_in"))
      (node (ref "U1") (pin "11") (pinfunction "VDD_11") (pintype "power_in"))
      (node (ref "U1") (pin "27") (pinfunction "VDD_27") (pintype "power_in"))
      (node (ref "U1") (pin "50") (pinfunction "VDD_50") (pintype "power_in"))
      (node (ref "U1") (pin "6") (pinfunction "VBAT_6") (pintype "power_in"))
      (node (ref "U1") (pin "75") (pinfunction "VDD_75") (pintype "power_in"))
      (node (ref "U12") (pin "4") (pinfunction "VOUT_4") (pintype "output"))
      (node (ref "U2") (pin "5") (pinfunction "VDDIO_5") (pintype "power_in"))
      (node (ref "U5") (pin "4") (pinfunction "VCC_4") (pintype "power_in"))
    )
    (net (code "41") (name "7.4V") (class "Default")
      (node (ref "C13") (pin "2") (pinfunction "2_2") (pintype "passive"))
      (node (ref "C16") (pin "2") (pinfunction "2_2") (pintype "passive"))
      (node (ref "C17") (pin "1") (pinfunction "1_1") (pintype "passive"))
      (node (ref "C22") (pin "2") (pinfunction "2_2") (pintype "passive"))
      (node (ref "C23") (pin "1") (pinfunction "1_1") (pintype "passive"))
      (node (ref "S2") (pin "1") (pinfunction "COM_1") (pintype "passive"))
      (node (ref "U12") (pin "1") (pinfunction "EN_1") (pintype "input"))
      (node (ref "U12") (pin "2") (pinfunction "VIN_2") (pintype "input"))
      (node (ref "U3") (pin "11") (pinfunction "VM_11") (pintype "power_in"))
      (node (ref "U4") (pin "11") (pinfunction "VM_11") (pintype "power_in"))
    )
    (net (code "42") (name "BAT") (class "Default")
      (node (ref "J1") (pin "1") (pinfunction "1_1") (pintype "passive"))
      (node (ref "S2") (pin "2") (pinfunction "NO_2") (pintype "passive"))
    )
    (net (code "43") (name "GND") (class "Default")
      (node (ref "C1") (pin "2") (pinfunction "2_2") (pintype "passive"))
      (node (ref "C10") (pin "1") (pinfunction "1_1") (pintype "passive"))
      (node (ref "C11") (pin "2") (pinfunction "2_2") (pintype "passive"))
      (node (ref "C12") (pin "1") (pinfunction "1_1") (pintype "passive"))
      (node (ref "C13") (pin "1") (pinfunction "1_1") (pintype "passive"))
      (node (ref "C14") (pin "1") (pinfunction "1_1") (pintype "passive"))
      (node (ref "C16") (pin "1") (pinfunction "1_1") (pintype "passive"))
      (node (ref "C17") (pin "2") (pinfunction "2_2") (pintype "passive"))
      (node (ref "C19") (pin "1") (pinfunction "1_1") (pintype "passive"))
      (node (ref "C2") (pin "2") (pinfunction "2_2") (pintype "passive"))
      (node (ref "C20") (pin "1") (pinfunction "1_1") (pintype "passive"))
      (node (ref "C22") (pin "1") (pinfunction "1_1") (pintype "passive"))
      (node (ref "C23") (pin "2") (pinfunction "2_2") (pintype "passive"))
      (node (ref "C25") (pin "1") (pinfunction "1_1") (pintype "passive"))
      (node (ref "C26") (pin "1") (pinfunction "1_1") (pintype "passive"))
      (node (ref "C27") (pin "1") (pinfunction "1_1") (pintype "passive"))
      (node (ref "C28") (pin "2") (pinfunction "2_2") (pintype "passive"))
      (node (ref "C29") (pin "1") (pinfunction "1_1") (pintype "passive"))
      (node (ref "C3") (pin "1") (pinfunction "1_1") (pintype "passive"))
      (node (ref "C30") (pin "1") (pinfunction "1_1") (pintype "passive"))
      (node (ref "C31") (pin "1") (pinfunction "1_1") (pintype "passive"))
      (node (ref "C4") (pin "1") (pinfunction "1_1") (pintype "passive"))
      (node (ref "C5") (pin "1") (pinfunction "1_1") (pintype "passive"))
      (node (ref "C6") (pin "1") (pinfunction "1_1") (pintype "passive"))
      (node (ref "C7") (pin "1") (pinfunction "1_1") (pintype "passive"))
      (node (ref "C8") (pin "1") (pinfunction "1_1") (pintype "passive"))
      (node (ref "C9") (pin "1") (pinfunction "1_1") (pintype "passive"))
      (node (ref "J1") (pin "2") (pinfunction "2_2") (pintype "passive"))
      (node (ref "J2") (pin "10") (pinfunction "10_10") (pintype "passive"))
      (node (ref "J2") (pin "6") (pinfunction "6_6") (pintype "passive"))
      (node (ref "J2") (pin "8") (pinfunction "8_8") (pintype "passive"))
      (node (ref "R1") (pin "1") (pinfunction "1_1") (pintype "passive"))
      (node (ref "R3") (pin "1") (pinfunction "1_1") (pintype "passive"))
      (node (ref "R4") (pin "1") (pinfunction "1_1") (pintype "passive"))
      (node (ref "R9") (pin "1") (pinfunction "1_1") (pintype "passive"))
      (node (ref "U1") (pin "10") (pinfunction "VSS_10") (pintype "power_in"))
      (node (ref "U1") (pin "19") (pinfunction "VSSA_19") (pintype "power_in"))
      (node (ref "U1") (pin "26") (pinfunction "VSS_26") (pintype "power_in"))
      (node (ref "U1") (pin "49") (pinfunction "VSS_49") (pintype "power_in"))
      (node (ref "U1") (pin "74") (pinfunction "VSS_74") (pintype "power_in"))
      (node (ref "U1") (pin "99") (pinfunction "VSS_99") (pintype "power_in"))
      (node (ref "U12") (pin "10") (pinfunction "GND_10") (pintype "power_in"))
      (node (ref "U12") (pin "11") (pinfunction "GND_11") (pintype "power_in"))
      (node (ref "U12") (pin "12") (pinfunction "GND_12") (pintype "power_in"))
      (node (ref "U12") (pin "3") (pinfunction "GND_3") (pintype "power_in"))
      (node (ref "U12") (pin "9") (pinfunction "GND_9") (pintype "power_in"))
      (node (ref "U2") (pin "10") (pinfunction "RESV_10_10") (pintype "passive"))
      (node (ref "U2") (pin "11") (pinfunction "RESV_11_11") (pintype "passive"))
      (node (ref "U2") (pin "2") (pinfunction "RESV_2_2") (pintype "passive"))
      (node (ref "U2") (pin "3") (pinfunction "RESV_3_3") (pintype "passive"))
      (node (ref "U2") (pin "6") (pinfunction "GND_6") (pintype "power_in"))
      (node (ref "U2") (pin "7") (pinfunction "RESV_7_7") (pintype "passive"))
      (node (ref "U2") (pin "9") (pinfunction "INT2/FSYNC/CLKIN_9") (pintype "bidirectional"))
      (node (ref "U3") (pin "15") (pinfunction "GND_15") (pintype "power_in"))
      (node (ref "U3") (pin "16") (pinfunction "PMODE_16") (pintype "input"))
      (node (ref "U3") (pin "7") (pinfunction "IMODE_7") (pintype "input"))
      (node (ref "U3") (pin "9") (pinfunction "PGND_9") (pintype "power_in"))
      (node (ref "U4") (pin "15") (pinfunction "GND_15") (pintype "power_in"))
      (node (ref "U4") (pin "16") (pinfunction "PMODE_16") (pintype "input"))
      (node (ref "U4") (pin "7") (pinfunction "IMODE_7") (pintype "input"))
      (node (ref "U4") (pin "9") (pinfunction "PGND_9") (pintype "power_in"))
      (node (ref "U5") (pin "14") (pinfunction "GND_14") (pintype "power_in"))
      (node (ref "U5") (pin "5") (pinfunction "GND_5") (pintype "power_in"))
      (node (ref "U6") (pin "2") (pinfunction "C_2") (pintype "passive"))
      (node (ref "U6") (pin "4") (pinfunction "ET_4") (pintype "passive"))
      (node (ref "U7") (pin "2") (pinfunction "C_2") (pintype "passive"))
      (node (ref "U7") (pin "4") (pinfunction "ET_4") (pintype "passive"))
    )
    (net (code "44") (name "Net-(M1-+)") (class "Default")
      (node (ref "M1") (pin "1") (pinfunction "+_1") (pintype "passive"))
      (node (ref "U3") (pin "8") (pinfunction "OUT1_8") (pintype "output"))
    )
    (net (code "45") (name "Net-(M1--)") (class "Default")
      (node (ref "M1") (pin "2") (pinfunction "-_2") (pintype "passive"))
      (node (ref "U3") (pin "10") (pinfunction "OUT2_10") (pintype "output"))
    )
    (net (code "46") (name "Net-(M2-+)") (class "Default")
      (node (ref "M2") (pin "1") (pinfunction "+_1") (pintype "passive"))
      (node (ref "U4") (pin "8") (pinfunction "OUT1_8") (pintype "output"))
    )
    (net (code "47") (name "Net-(M2--)") (class "Default")
      (node (ref "M2") (pin "2") (pinfunction "-_2") (pintype "passive"))
      (node (ref "U4") (pin "10") (pinfunction "OUT2_10") (pintype "output"))
    )
    (net (code "48") (name "Net-(U1-VDDA)") (class "Default")
      (node (ref "C1") (pin "1") (pinfunction "1_1") (pintype "passive"))
      (node (ref "C2") (pin "1") (pinfunction "1_1") (pintype "passive"))
      (node (ref "FL1") (pin "1") (pinfunction "1_1") (pintype "passive"))
      (node (ref "U1") (pin "20") (pinfunction "VREF+_20") (pintype "power_in"))
      (node (ref "U1") (pin "21") (pinfunction "VDDA_21") (pintype "power_in"))
    )
    (net (code "49") (name "Net-(U2-VDD)") (class "Default")
      (node (ref "C25") (pin "2") (pinfunction "2_2") (pintype "passive"))
      (node (ref "C26") (pin "2") (pinfunction "2_2") (pintype "passive"))
      (node (ref "FL2") (pin "1") (pinfunction "1_1") (pintype "passive"))
      (node (ref "U2") (pin "8") (pinfunction "VDD_8") (pintype "power_in"))
    )
    (net (code "50") (name "Net-(U3-CPH)") (class "Default")
      (node (ref "C15") (pin "2") (pinfunction "2_2") (pintype "passive"))
      (node (ref "U3") (pin "13") (pinfunction "CPH_13") (pintype "power_in"))
    )
    (net (code "51") (name "Net-(U3-CPL)") (class "Default")
      (node (ref "C15") (pin "1") (pinfunction "1_1") (pintype "passive"))
      (node (ref "U3") (pin "14") (pinfunction "CPL_14") (pintype "power_in"))
    )
    (net (code "52") (name "Net-(U4-CPH)") (class "Default")
      (node (ref "C21") (pin "2") (pinfunction "2_2") (pintype "passive"))
      (node (ref "U4") (pin "13") (pinfunction "CPH_13") (pintype "power_in"))
    )
    (net (code "53") (name "Net-(U4-CPL)") (class "Default")
      (node (ref "C21") (pin "1") (pinfunction "1_1") (pintype "passive"))
      (node (ref "U4") (pin "14") (pinfunction "CPL_14") (pintype "power_in"))
    )
    (net (code "54") (name "Net-(U5-LINK(P0.16))") (class "Default")
      (node (ref "D1") (pin "C") (pinfunction "C_C") (pintype "passive"))
      (node (ref "U5") (pin "13") (pinfunction "LINK(P0.16)_13") (pintype "bidirectional"))
    )
    (net (code "55") (name "Net-(U6-A)") (class "Default")
      (node (ref "R14") (pin "2") (pinfunction "2_2") (pintype "passive"))
      (node (ref "U6") (pin "1") (pinfunction "A_1") (pintype "passive"))
    )
    (net (code "56") (name "Net-(U7-A)") (class "Default")
      (node (ref "R11") (pin "2") (pinfunction "2_2") (pintype "passive"))
      (node (ref "U7") (pin "1") (pinfunction "A_1") (pintype "passive"))
    )
    (net (code "57") (name "Net-(U12-SS{slash}TR)") (class "Default")
      (node (ref "C12") (pin "2") (pinfunction "2_2") (pintype "passive"))
      (node (ref "U12") (pin "8") (pinfunction "SS/TR_8") (pintype "input"))
    )
    (net (code "58") (name "unconnected-(C18-Pad1)") (class "Default")
      (node (ref "C18") (pin "1") (pinfunction "1_1") (pintype "passive"))
    )
    (net (code "59") (name "unconnected-(C24-Pad1)") (class "Default")
      (node (ref "C24") (pin "1") (pinfunction "1_1") (pintype "passive"))
    )
    (net (code "60") (name "unconnected-(D1-PadA)") (class "Default")
      (node (ref "D1") (pin "A") (pinfunction "A_A") (pintype "passive"))
    )
    (net (code "61") (name "unconnected-(R12-Pad1)") (class "Default")
      (node (ref "R12") (pin "1") (pinfunction "1_1") (pintype "passive"))
    )
    (net (code "62") (name "unconnected-(U1-PA0-Pad22)") (class "Default")
      (node (ref "U1") (pin "22") (pinfunction "PA0_22") (pintype "bidirectional"))
    )
    (net (code "63") (name "unconnected-(U1-PA1-Pad23)") (class "Default")
      (node (ref "U1") (pin "23") (pinfunction "PA1_23") (pintype "bidirectional"))
    )
    (net (code "64") (name "unconnected-(U1-PA2-Pad24)") (class "Default")
      (node (ref "U1") (pin "24") (pinfunction "PA2_24") (pintype "bidirectional"))
    )
    (net (code "65") (name "unconnected-(U1-PA3-Pad25)") (class "Default")
      (node (ref "U1") (pin "25") (pinfunction "PA3_25") (pintype "bidirectional"))
    )
    (net (code "66") (name "unconnected-(U1-PA6-Pad30)") (class "Default")
      (node (ref "U1") (pin "30") (pinfunction "PA6_30") (pintype "bidirectional"))
    )
    (net (code "67") (name "unconnected-(U1-PA7-Pad31)") (class "Default")
      (node (ref "U1") (pin "31") (pinfunction "PA7_31") (pintype "bidirectional"))
    )
    (net (code "68") (name "unconnected-(U1-PA8-Pad67)") (class "Default")
      (node (ref "U1") (pin "67") (pinfunction "PA8_67") (pintype "bidirectional"))
    )
    (net (code "69") (name "unconnected-(U1-PA11-Pad70)") (class "Default")
      (node (ref "U1") (pin "70") (pinfunction "PA11_70") (pintype "bidirectional"))
    )
    (net (code "70") (name "unconnected-(U1-PA12-Pad71)") (class "Default")
      (node (ref "U1") (pin "71") (pinfunction "PA12_71") (pintype "bidirectional"))
    )
    (net (code "71") (name "unconnected-(U1-PA15-Pad77)") (class "Default")
      (node (ref "U1") (pin "77") (pinfunction "PA15_77") (pintype "bidirectional"))
    )
    (net (code "72") (name "unconnected-(U1-PB0-Pad34)") (class "Default")
      (node (ref "U1") (pin "34") (pinfunction "PB0_34") (pintype "bidirectional"))
    )
    (net (code "73") (name "unconnected-(U1-PB1-Pad35)") (class "Default")
      (node (ref "U1") (pin "35") (pinfunction "PB1_35") (pintype "bidirectional"))
    )
    (net (code "74") (name "unconnected-(U1-PB2-Pad36)") (class "Default")
      (node (ref "U1") (pin "36") (pinfunction "PB2_36") (pintype "bidirectional"))
    )
    (net (code "75") (name "unconnected-(U1-PB4-Pad90)") (class "Default")
      (node (ref "U1") (pin "90") (pinfunction "PB4_90") (pintype "bidirectional"))
    )
    (net (code "76") (name "unconnected-(U1-PB5-Pad91)") (class "Default")
      (node (ref "U1") (pin "91") (pinfunction "PB5_91") (pintype "bidirectional"))
    )
    (net (code "77") (name "unconnected-(U1-PB7-Pad93)") (class "Default")
      (node (ref "U1") (pin "93") (pinfunction "PB7_93") (pintype "bidirectional"))
    )
    (net (code "78") (name "unconnected-(U1-PB8-Pad95)") (class "Default")
      (node (ref "U1") (pin "95") (pinfunction "PB8_95") (pintype "bidirectional"))
    )
    (net (code "79") (name "unconnected-(U1-PB9-Pad96)") (class "Default")
      (node (ref "U1") (pin "96") (pinfunction "PB9_96") (pintype "bidirectional"))
    )
    (net (code "80") (name "unconnected-(U1-PB10-Pad46)") (class "Default")
      (node (ref "U1") (pin "46") (pinfunction "PB10_46") (pintype "bidirectional"))
    )
    (net (code "81") (name "unconnected-(U1-PB11-Pad47)") (class "Default")
      (node (ref "U1") (pin "47") (pinfunction "PB11_47") (pintype "bidirectional"))
    )
    (net (code "82") (name "unconnected-(U1-PB12-Pad51)") (class "Default")
      (node (ref "U1") (pin "51") (pinfunction "PB12_51") (pintype "bidirectional"))
    )
    (net (code "83") (name "unconnected-(U1-PC2_C-Pad17)") (class "Default")
      (node (ref "U1") (pin "17") (pinfunction "PC2_C_17") (pintype "bidirectional"))
    )
    (net (code "84") (name "unconnected-(U1-PC3_C-Pad18)") (class "Default")
      (node (ref "U1") (pin "18") (pinfunction "PC3_C_18") (pintype "bidirectional"))
    )
    (net (code "85") (name "unconnected-(U1-PC10-Pad78)") (class "Default")
      (node (ref "U1") (pin "78") (pinfunction "PC10_78") (pintype "bidirectional"))
    )
    (net (code "86") (name "unconnected-(U1-PC11-Pad79)") (class "Default")
      (node (ref "U1") (pin "79") (pinfunction "PC11_79") (pintype "bidirectional"))
    )
    (net (code "87") (name "unconnected-(U1-PC12-Pad80)") (class "Default")
      (node (ref "U1") (pin "80") (pinfunction "PC12_80") (pintype "bidirectional"))
    )
    (net (code "88") (name "unconnected-(U1-PC13-Pad7)") (class "Default")
      (node (ref "U1") (pin "7") (pinfunction "PC13_7") (pintype "bidirectional"))
    )
    (net (code "89") (name "unconnected-(U1-PC14-OSC32_IN-Pad8)") (class "Default")
      (node (ref "U1") (pin "8") (pinfunction "PC14-OSC32_IN_8") (pintype "bidirectional"))
    )
    (net (code "90") (name "unconnected-(U1-PC15-OSC32_OUT-Pad9)") (class "Default")
      (node (ref "U1") (pin "9") (pinfunction "PC15-OSC32_OUT_9") (pintype "bidirectional"))
    )
    (net (code "91") (name "unconnected-(U1-PD2-Pad83)") (class "Default")
      (node (ref "U1") (pin "83") (pinfunction "PD2_83") (pintype "bidirectional"))
    )
    (net (code "92") (name "unconnected-(U1-PD3-Pad84)") (class "Default")
      (node (ref "U1") (pin "84") (pinfunction "PD3_84") (pintype "bidirectional"))
    )
    (net (code "93") (name "unconnected-(U1-PD4-Pad85)") (class "Default")
      (node (ref "U1") (pin "85") (pinfunction "PD4_85") (pintype "bidirectional"))
    )
    (net (code "94") (name "unconnected-(U1-PD5-Pad86)") (class "Default")
      (node (ref "U1") (pin "86") (pinfunction "PD5_86") (pintype "bidirectional"))
    )
    (net (code "95") (name "unconnected-(U1-PD7-Pad88)") (class "Default")
      (node (ref "U1") (pin "88") (pinfunction "PD7_88") (pintype "bidirectional"))
    )
    (net (code "96") (name "unconnected-(U1-PD10-Pad57)") (class "Default")
      (node (ref "U1") (pin "57") (pinfunction "PD10_57") (pintype "bidirectional"))
    )
    (net (code "97") (name "unconnected-(U1-PD11-Pad58)") (class "Default")
      (node (ref "U1") (pin "58") (pinfunction "PD11_58") (pintype "bidirectional"))
    )
    (net (code "98") (name "unconnected-(U1-PD12-Pad59)") (class "Default")
      (node (ref "U1") (pin "59") (pinfunction "PD12_59") (pintype "bidirectional"))
    )
    (net (code "99") (name "unconnected-(U1-PD13-Pad60)") (class "Default")
      (node (ref "U1") (pin "60") (pinfunction "PD13_60") (pintype "bidirectional"))
    )
    (net (code "100") (name "unconnected-(U1-PD14-Pad61)") (class "Default")
      (node (ref "U1") (pin "61") (pinfunction "PD14_61") (pintype "bidirectional"))
    )
    (net (code "101") (name "unconnected-(U1-PD15-Pad62)") (class "Default")
      (node (ref "U1") (pin "62") (pinfunction "PD15_62") (pintype "bidirectional"))
    )
    (net (code "102") (name "unconnected-(U1-PE0-Pad97)") (class "Default")
      (node (ref "U1") (pin "97") (pinfunction "PE0_97") (pintype "bidirectional"))
    )
    (net (code "103") (name "unconnected-(U1-PE1-Pad98)") (class "Default")
      (node (ref "U1") (pin "98") (pinfunction "PE1_98") (pintype "bidirectional"))
    )
    (net (code "104") (name "unconnected-(U1-PE2-Pad1)") (class "Default")
      (node (ref "U1") (pin "1") (pinfunction "PE2_1") (pintype "bidirectional"))
    )
    (net (code "105") (name "unconnected-(U1-PE4-Pad3)") (class "Default")
      (node (ref "U1") (pin "3") (pinfunction "PE4_3") (pintype "bidirectional"))
    )
    (net (code "106") (name "unconnected-(U1-PE5-Pad4)") (class "Default")
      (node (ref "U1") (pin "4") (pinfunction "PE5_4") (pintype "bidirectional"))
    )
    (net (code "107") (name "unconnected-(U1-PE6-Pad5)") (class "Default")
      (node (ref "U1") (pin "5") (pinfunction "PE6_5") (pintype "bidirectional"))
    )
    (net (code "108") (name "unconnected-(U1-PE7-Pad37)") (class "Default")
      (node (ref "U1") (pin "37") (pinfunction "PE7_37") (pintype "bidirectional"))
    )
    (net (code "109") (name "unconnected-(U1-PE8-Pad38)") (class "Default")
      (node (ref "U1") (pin "38") (pinfunction "PE8_38") (pintype "bidirectional"))
    )
    (net (code "110") (name "unconnected-(U1-PE14-Pad44)") (class "Default")
      (node (ref "U1") (pin "44") (pinfunction "PE14_44") (pintype "bidirectional"))
    )
    (net (code "111") (name "unconnected-(U1-PE15-Pad45)") (class "Default")
      (node (ref "U1") (pin "45") (pinfunction "PE15_45") (pintype "bidirectional"))
    )
    (net (code "112") (name "unconnected-(U1-PH0-OSC_IN-Pad12)") (class "Default")
      (node (ref "U1") (pin "12") (pinfunction "PH0-OSC_IN_12") (pintype "bidirectional"))
    )
    (net (code "113") (name "unconnected-(U1-PH1-OSC_OUT-Pad13)") (class "Default")
      (node (ref "U1") (pin "13") (pinfunction "PH1-OSC_OUT_13") (pintype "bidirectional"))
    )
    (net (code "114") (name "unconnected-(U5-P0.00-Pad8)") (class "Default")
      (node (ref "U5") (pin "8") (pinfunction "P0.00_8") (pintype "bidirectional"))
    )
    (net (code "115") (name "unconnected-(U5-P0.01-Pad10)") (class "Default")
      (node (ref "U5") (pin "10") (pinfunction "P0.01_10") (pintype "bidirectional"))
    )
    (net (code "116") (name "unconnected-(U5-SWCLK-Pad2)") (class "Default")
      (node (ref "U5") (pin "2") (pinfunction "SWCLK_2") (pintype "bidirectional"))
    )
    (net (code "117") (name "unconnected-(U5-SWDIO-Pad1)") (class "Default")
      (node (ref "U5") (pin "1") (pinfunction "SWDIO_1") (pintype "bidirectional"))
    )
    (net (code "118") (name "unconnected-(U12-PG-Pad7)") (class "Default")
      (node (ref "U12") (pin "7") (pinfunction "PG_7") (pintype "output"))
    )
    (net (code "119") (name "unconnected-(U12-VOUT-Pad5)") (class "Default")
      (node (ref "U12") (pin "5") (pinfunction "VOUT_5") (pintype "output"))
    )
  )
)
